# CKLink_Lite.net
KiCad netlist of a schematic drawn in Altium Designer
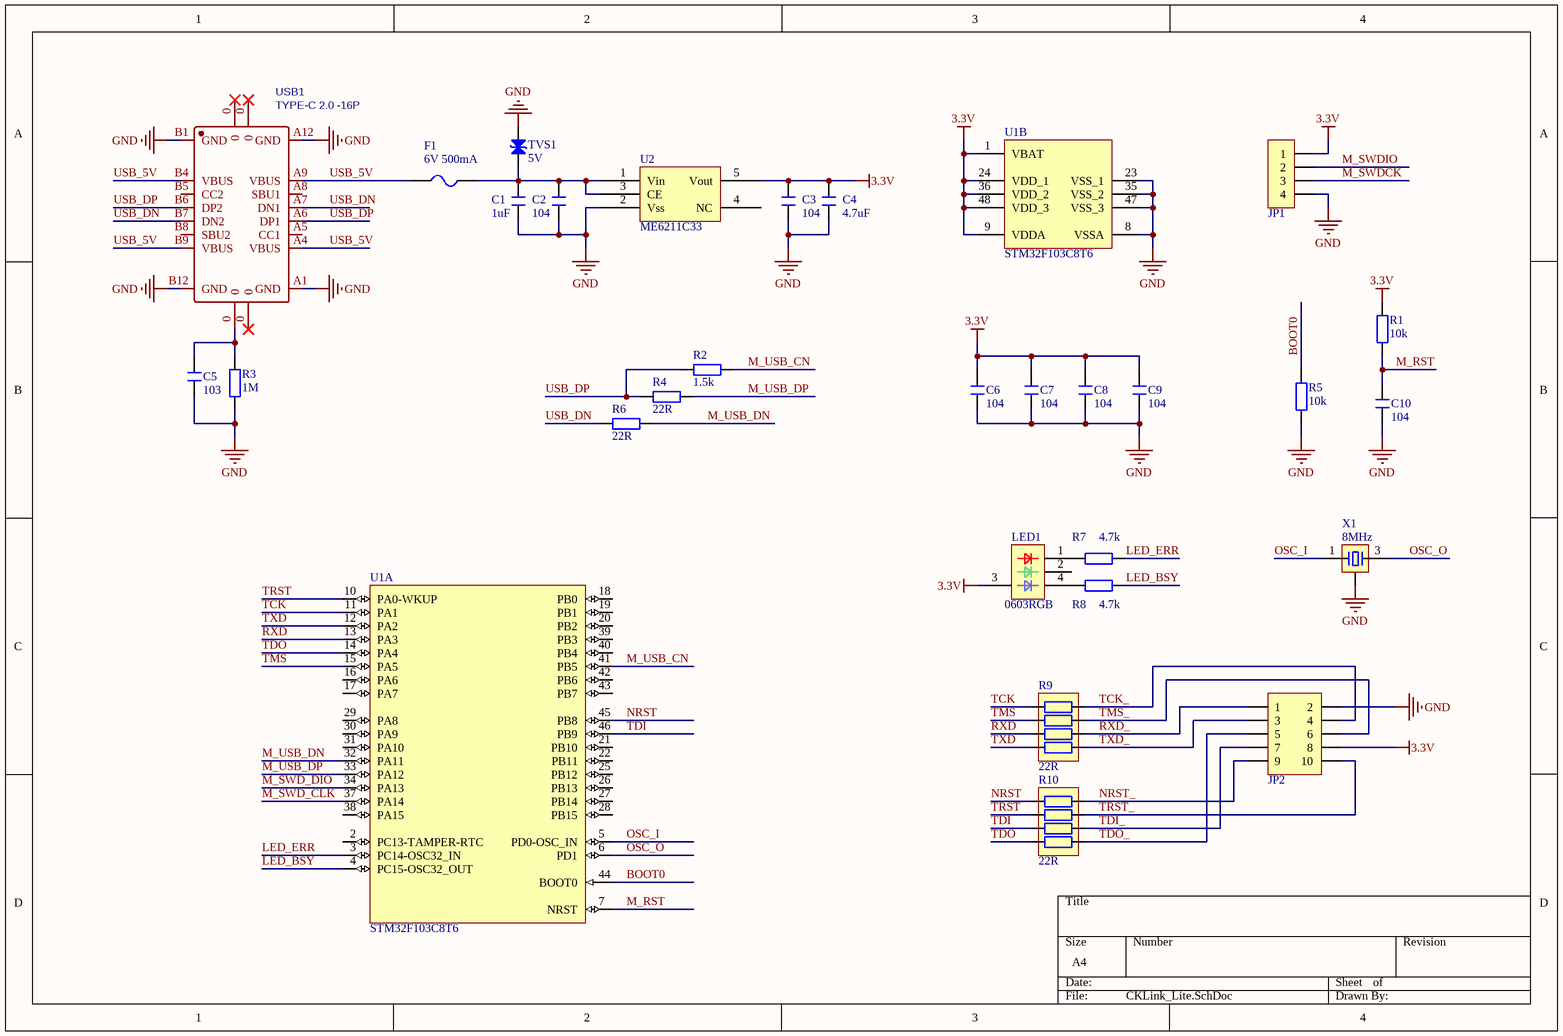
[diagram p0: CKLink_Lite.SchDoc]

(export (version "E")
  (design (tool "Eeschema 10.0.6"))
  (components
    (comp (ref "C1")
      (value "1uF")
      (footprint "C 0603_L")
      (description "贴片电容")
      (libsource (lib "0.1 - 电阻-电容-电感") (part "C"))
    )
    (comp (ref "C2")
      (value "104")
      (footprint "C 0603_L")
      (description "贴片电容")
      (libsource (lib "0.1 - 电阻-电容-电感") (part "C"))
    )
    (comp (ref "C3")
      (value "104")
      (footprint "C 0603_L")
      (description "贴片电容")
      (libsource (lib "0.1 - 电阻-电容-电感") (part "C"))
    )
    (comp (ref "C4")
      (value "4.7uF")
      (footprint "C 0603_L")
      (description "贴片电容")
      (libsource (lib "0.1 - 电阻-电容-电感") (part "C"))
    )
    (comp (ref "C5")
      (value "103")
      (footprint "C 0603_L")
      (description "贴片电容")
      (libsource (lib "0.1 - 电阻-电容-电感") (part "C"))
    )
    (comp (ref "C6")
      (value "104")
      (footprint "C 0603_L")
      (description "贴片电容")
      (libsource (lib "0.1 - 电阻-电容-电感") (part "C"))
    )
    (comp (ref "C7")
      (value "104")
      (footprint "C 0603_L")
      (description "贴片电容")
      (libsource (lib "0.1 - 电阻-电容-电感") (part "C"))
    )
    (comp (ref "C8")
      (value "104")
      (footprint "C 0603_L")
      (description "贴片电容")
      (libsource (lib "0.1 - 电阻-电容-电感") (part "C"))
    )
    (comp (ref "C9")
      (value "104")
      (footprint "C 0603_L")
      (description "贴片电容")
      (libsource (lib "0.1 - 电阻-电容-电感") (part "C"))
    )
    (comp (ref "C10")
      (value "104")
      (footprint "C 0603_L")
      (description "贴片电容")
      (libsource (lib "0.1 - 电阻-电容-电感") (part "C"))
    )
    (comp (ref "F1")
      (value "6V 500mA")
      (footprint "FU 0805")
      (description "贴片保险丝")
      (fields (field (name "版权归属") "封装库来自淘宝卖家 ID：黄晶宝石"))
      (libsource (lib "0.5 - 保险丝-晶振-光耦") (part "FU"))
    )
    (comp (ref "JP1")
      (value "HDR-1X4")
      (footprint "HDR2.54-LI-4P")
      (description "4P接插件")
      (fields (field (name "版权归属") "封装库来自淘宝 ID：黄晶宝石"))
      (libsource (lib "5.4 - 接插件-脚距2.54 (100mil) ") (part "Header 4"))
    )
    (comp (ref "JP2")
      (value "Header 5X2")
      (footprint "CHE2*5")
      (description "5*2P接插件")
      (fields (field (name "版权归属") "封装库来自淘宝 ID：黄晶宝石"))
      (libsource (lib "5.4 - 接插件-脚距2.54 (100mil) ") (part "Header 5X2"))
    )
    (comp (ref "LED1")
      (value "0603RGB")
      (footprint "0603RGB")
      (libsource (lib "0.3 - LED发光二极管") (part "0603RGB"))
    )
    (comp (ref "R1")
      (value "10k")
      (footprint "R 0603_L")
      (description "贴片电阻")
      (libsource (lib "0.1 - 电阻-电容-电感") (part "R"))
    )
    (comp (ref "R2")
      (value "1.5k")
      (footprint "R 0603_L")
      (description "贴片电阻")
      (libsource (lib "0.1 - 电阻-电容-电感") (part "R"))
    )
    (comp (ref "R3")
      (value "1M")
      (footprint "R 0603_L")
      (description "贴片电阻")
      (libsource (lib "0.1 - 电阻-电容-电感") (part "R"))
    )
    (comp (ref "R4")
      (value "22R")
      (footprint "R 0603_L")
      (description "贴片电阻")
      (libsource (lib "0.1 - 电阻-电容-电感") (part "R"))
    )
    (comp (ref "R5")
      (value "10k")
      (footprint "R 0603_L")
      (description "贴片电阻")
      (libsource (lib "0.1 - 电阻-电容-电感") (part "R"))
    )
    (comp (ref "R6")
      (value "22R")
      (footprint "R 0603_L")
      (description "贴片电阻")
      (libsource (lib "0.1 - 电阻-电容-电感") (part "R"))
    )
    (comp (ref "R7")
      (value "4.7k")
      (footprint "R 0603_L")
      (description "贴片电阻")
      (libsource (lib "0.1 - 电阻-电容-电感") (part "R"))
    )
    (comp (ref "R8")
      (value "4.7k")
      (footprint "R 0603_L")
      (description "贴片电阻")
      (libsource (lib "0.1 - 电阻-电容-电感") (part "R"))
    )
    (comp (ref "R9")
      (value "22R")
      (footprint "RCA-8P4R-0603")
      (description "贴片排阻")
      (libsource (lib "0.1 - 电阻-电容-电感") (part "R-8P4R"))
    )
    (comp (ref "R10")
      (value "22R")
      (footprint "RCA-8P4R-0603")
      (description "贴片排阻")
      (libsource (lib "") (part "R-8P4R_1"))
    )
    (comp (ref "TVS1")
      (value "5V")
      (footprint "SOD-323")
      (description "TVS保护")
      (libsource (lib "0.2 - 二极管-整流桥") (part "TVS"))
    )
    (comp (ref "U1")
      (value "STM32F103C8T6")
      (footprint "LQFP48_L")
      (libsource (lib "2.3 - STM32 F1系列单片机") (part "STM32F103C8T6"))
    )
    (comp (ref "U2")
      (value "ME6211C33")
      (footprint "SOT23-5N")
      (description "3.3V 500mA 低压差线性稳压器")
      (libsource (lib "1.1 - 电源类芯片") (part "ME6211C33"))
    )
    (comp (ref "USB1")
      (value "TYPE-C 2.0 -16P")
      (footprint "USB-TYPE-C_16PIN-MALE-TYPE-C-31-M-12")
      (description "USB2.0 Type-C 母座 16Pin")
      (libsource (lib "0.8 - 以太网-音频-USB插座") (part "USB2.0 Type-C 16Pin母座"))
    )
    (comp (ref "X1")
      (value "8MHz")
      (footprint "CSTCE 3pin")
      (description "3脚无源晶振")
      (fields (field (name "版权归属") "封装库来自淘宝卖家 ID：黄晶宝石"))
      (libsource (lib "0.5 - 保险丝-晶振-光耦") (part "XTAL-3P"))
    )
  )
  (nets
    (net (code "1") (name "/BOOT0") (class "Default")
      (node (ref "R5") (pin "2") (pinfunction "2_2") (pintype "passive"))
      (node (ref "U1") (pin "44") (pinfunction "BOOT0_44") (pintype "input"))
    )
    (net (code "2") (name "/LED_BSY") (class "Default")
      (node (ref "R8") (pin "1") (pinfunction "1_1") (pintype "passive"))
      (node (ref "U1") (pin "4") (pinfunction "PC15-OSC32_OUT_4") (pintype "bidirectional"))
    )
    (net (code "3") (name "/LED_ERR") (class "Default")
      (node (ref "R7") (pin "1") (pinfunction "1_1") (pintype "passive"))
      (node (ref "U1") (pin "3") (pinfunction "PC14-OSC32_IN_3") (pintype "bidirectional"))
    )
    (net (code "4") (name "/M_RST") (class "Default")
      (node (ref "C10") (pin "2") (pinfunction "2_2") (pintype "passive"))
      (node (ref "R1") (pin "1") (pinfunction "1_1") (pintype "passive"))
      (node (ref "U1") (pin "7") (pinfunction "NRST_7") (pintype "bidirectional"))
    )
    (net (code "5") (name "/M_SWDCK") (class "Default")
      (node (ref "JP1") (pin "3") (pinfunction "3_3") (pintype "passive"))
    )
    (net (code "6") (name "/M_SWDIO") (class "Default")
      (node (ref "JP1") (pin "2") (pinfunction "2_2") (pintype "passive"))
    )
    (net (code "7") (name "/M_SWD_CLK") (class "Default")
      (node (ref "U1") (pin "37") (pinfunction "PA14_37") (pintype "bidirectional"))
    )
    (net (code "8") (name "/M_SWD_DIO") (class "Default")
      (node (ref "U1") (pin "34") (pinfunction "PA13_34") (pintype "bidirectional"))
    )
    (net (code "9") (name "/M_USB_CN") (class "Default")
      (node (ref "R2") (pin "1") (pinfunction "1_1") (pintype "passive"))
      (node (ref "U1") (pin "41") (pinfunction "PB5_41") (pintype "bidirectional"))
    )
    (net (code "10") (name "/M_USB_DN") (class "Default")
      (node (ref "R6") (pin "1") (pinfunction "1_1") (pintype "passive"))
      (node (ref "U1") (pin "32") (pinfunction "PA11_32") (pintype "bidirectional"))
    )
    (net (code "11") (name "/M_USB_DP") (class "Default")
      (node (ref "R4") (pin "1") (pinfunction "1_1") (pintype "passive"))
      (node (ref "U1") (pin "33") (pinfunction "PA12_33") (pintype "bidirectional"))
    )
    (net (code "12") (name "/NRST") (class "Default")
      (node (ref "R10") (pin "4") (pinfunction "4_4") (pintype "passive"))
      (node (ref "U1") (pin "45") (pinfunction "PB8_45") (pintype "bidirectional"))
    )
    (net (code "13") (name "/NRST_") (class "Default")
      (node (ref "JP2") (pin "9") (pinfunction "9_9") (pintype "passive"))
      (node (ref "R10") (pin "5") (pinfunction "5_5") (pintype "passive"))
    )
    (net (code "14") (name "/OSC_I") (class "Default")
      (node (ref "U1") (pin "5") (pinfunction "PD0-OSC_IN_5") (pintype "bidirectional"))
      (node (ref "X1") (pin "1") (pinfunction "1_1") (pintype "passive"))
    )
    (net (code "15") (name "/OSC_O") (class "Default")
      (node (ref "U1") (pin "6") (pinfunction "PD1_6") (pintype "bidirectional"))
      (node (ref "X1") (pin "3") (pinfunction "3_3") (pintype "passive"))
    )
    (net (code "16") (name "/RXD") (class "Default")
      (node (ref "R9") (pin "3") (pinfunction "3_3") (pintype "passive"))
      (node (ref "U1") (pin "13") (pinfunction "PA3_13") (pintype "bidirectional"))
    )
    (net (code "17") (name "/RXD_") (class "Default")
      (node (ref "JP2") (pin "1") (pinfunction "1_1") (pintype "passive"))
      (node (ref "R9") (pin "6") (pinfunction "6_6") (pintype "passive"))
    )
    (net (code "18") (name "/TCK") (class "Default")
      (node (ref "R9") (pin "1") (pinfunction "1_1") (pintype "passive"))
      (node (ref "U1") (pin "11") (pinfunction "PA1_11") (pintype "bidirectional"))
    )
    (net (code "19") (name "/TCK_") (class "Default")
      (node (ref "JP2") (pin "4") (pinfunction "4_4") (pintype "passive"))
      (node (ref "R9") (pin "8") (pinfunction "8_8") (pintype "passive"))
    )
    (net (code "20") (name "/TDI") (class "Default")
      (node (ref "R10") (pin "2") (pinfunction "2_2") (pintype "passive"))
      (node (ref "U1") (pin "46") (pinfunction "PB9_46") (pintype "bidirectional"))
    )
    (net (code "21") (name "/TDI_") (class "Default")
      (node (ref "JP2") (pin "7") (pinfunction "7_7") (pintype "passive"))
      (node (ref "R10") (pin "7") (pinfunction "7_7") (pintype "passive"))
    )
    (net (code "22") (name "/TDO") (class "Default")
      (node (ref "R10") (pin "1") (pinfunction "1_1") (pintype "passive"))
      (node (ref "U1") (pin "14") (pinfunction "PA4_14") (pintype "bidirectional"))
    )
    (net (code "23") (name "/TDO_") (class "Default")
      (node (ref "JP2") (pin "5") (pinfunction "5_5") (pintype "passive"))
      (node (ref "R10") (pin "8") (pinfunction "8_8") (pintype "passive"))
    )
    (net (code "24") (name "/TMS") (class "Default")
      (node (ref "R9") (pin "2") (pinfunction "2_2") (pintype "passive"))
      (node (ref "U1") (pin "15") (pinfunction "PA5_15") (pintype "bidirectional"))
    )
    (net (code "25") (name "/TMS_") (class "Default")
      (node (ref "JP2") (pin "6") (pinfunction "6_6") (pintype "passive"))
      (node (ref "R9") (pin "7") (pinfunction "7_7") (pintype "passive"))
    )
    (net (code "26") (name "/TRST") (class "Default")
      (node (ref "R10") (pin "3") (pinfunction "3_3") (pintype "passive"))
      (node (ref "U1") (pin "10") (pinfunction "PA0-WKUP_10") (pintype "bidirectional"))
    )
    (net (code "27") (name "/TRST_") (class "Default")
      (node (ref "JP2") (pin "10") (pinfunction "10_10") (pintype "passive"))
      (node (ref "R10") (pin "6") (pinfunction "6_6") (pintype "passive"))
    )
    (net (code "28") (name "/TXD") (class "Default")
      (node (ref "R9") (pin "4") (pinfunction "4_4") (pintype "passive"))
      (node (ref "U1") (pin "12") (pinfunction "PA2_12") (pintype "bidirectional"))
    )
    (net (code "29") (name "/TXD_") (class "Default")
      (node (ref "JP2") (pin "3") (pinfunction "3_3") (pintype "passive"))
      (node (ref "R9") (pin "5") (pinfunction "5_5") (pintype "passive"))
    )
    (net (code "30") (name "/USB_5V") (class "Default")
      (node (ref "F1") (pin "1") (pinfunction "1_1") (pintype "passive"))
      (node (ref "USB1") (pin "A4") (pinfunction "VBUS_A4") (pintype "passive"))
      (node (ref "USB1") (pin "A9") (pinfunction "VBUS_A9") (pintype "passive"))
      (node (ref "USB1") (pin "B4") (pinfunction "VBUS_B4") (pintype "passive"))
      (node (ref "USB1") (pin "B9") (pinfunction "VBUS_B9") (pintype "passive"))
    )
    (net (code "31") (name "/USB_DN") (class "Default")
      (node (ref "R6") (pin "2") (pinfunction "2_2") (pintype "passive"))
      (node (ref "USB1") (pin "A7") (pinfunction "DN1_A7") (pintype "passive"))
      (node (ref "USB1") (pin "B7") (pinfunction "DN2_B7") (pintype "passive"))
    )
    (net (code "32") (name "/USB_DP") (class "Default")
      (node (ref "R2") (pin "2") (pinfunction "2_2") (pintype "passive"))
      (node (ref "R4") (pin "2") (pinfunction "2_2") (pintype "passive"))
      (node (ref "USB1") (pin "A6") (pinfunction "DP1_A6") (pintype "passive"))
      (node (ref "USB1") (pin "B6") (pinfunction "DP2_B6") (pintype "passive"))
    )
    (net (code "33") (name "3.3V") (class "Default")
      (node (ref "C3") (pin "2") (pinfunction "2_2") (pintype "passive"))
      (node (ref "C4") (pin "2") (pinfunction "2_2") (pintype "passive"))
      (node (ref "C6") (pin "2") (pinfunction "2_2") (pintype "passive"))
      (node (ref "C7") (pin "2") (pinfunction "2_2") (pintype "passive"))
      (node (ref "C8") (pin "2") (pinfunction "2_2") (pintype "passive"))
      (node (ref "C9") (pin "2") (pinfunction "2_2") (pintype "passive"))
      (node (ref "JP1") (pin "1") (pinfunction "1_1") (pintype "passive"))
      (node (ref "JP2") (pin "8") (pinfunction "8_8") (pintype "passive"))
      (node (ref "LED1") (pin "3") (pinfunction "VCC_3") (pintype "passive"))
      (node (ref "R1") (pin "2") (pinfunction "2_2") (pintype "passive"))
      (node (ref "U1") (pin "1") (pinfunction "VBAT_1") (pintype "power_in"))
      (node (ref "U1") (pin "24") (pinfunction "VDD_1_24") (pintype "power_in"))
      (node (ref "U1") (pin "36") (pinfunction "VDD_2_36") (pintype "power_in"))
      (node (ref "U1") (pin "48") (pinfunction "VDD_3_48") (pintype "power_in"))
      (node (ref "U1") (pin "9") (pinfunction "VDDA_9") (pintype "power_in"))
      (node (ref "U2") (pin "5") (pinfunction "Vout_5") (pintype "passive"))
    )
    (net (code "34") (name "GND") (class "Default")
      (node (ref "C1") (pin "1") (pinfunction "1_1") (pintype "passive"))
      (node (ref "C10") (pin "1") (pinfunction "1_1") (pintype "passive"))
      (node (ref "C2") (pin "1") (pinfunction "1_1") (pintype "passive"))
      (node (ref "C3") (pin "1") (pinfunction "1_1") (pintype "passive"))
      (node (ref "C4") (pin "1") (pinfunction "1_1") (pintype "passive"))
      (node (ref "C5") (pin "1") (pinfunction "1_1") (pintype "passive"))
      (node (ref "C6") (pin "1") (pinfunction "1_1") (pintype "passive"))
      (node (ref "C7") (pin "1") (pinfunction "1_1") (pintype "passive"))
      (node (ref "C8") (pin "1") (pinfunction "1_1") (pintype "passive"))
      (node (ref "C9") (pin "1") (pinfunction "1_1") (pintype "passive"))
      (node (ref "JP1") (pin "4") (pinfunction "4_4") (pintype "passive"))
      (node (ref "JP2") (pin "2") (pinfunction "2_2") (pintype "passive"))
      (node (ref "R3") (pin "1") (pinfunction "1_1") (pintype "passive"))
      (node (ref "R5") (pin "1") (pinfunction "1_1") (pintype "passive"))
      (node (ref "TVS1") (pin "2") (pinfunction "K_2") (pintype "passive"))
      (node (ref "U1") (pin "23") (pinfunction "VSS_1_23") (pintype "power_in"))
      (node (ref "U1") (pin "35") (pinfunction "VSS_2_35") (pintype "power_in"))
      (node (ref "U1") (pin "47") (pinfunction "VSS_3_47") (pintype "power_in"))
      (node (ref "U1") (pin "8") (pinfunction "VSSA_8") (pintype "power_in"))
      (node (ref "U2") (pin "2") (pinfunction "Vss_2") (pintype "passive"))
      (node (ref "USB1") (pin "A1") (pinfunction "GND_A1") (pintype "passive"))
      (node (ref "USB1") (pin "A12") (pinfunction "GND_A12") (pintype "passive"))
      (node (ref "USB1") (pin "B1") (pinfunction "GND_B1") (pintype "passive"))
      (node (ref "USB1") (pin "B12") (pinfunction "GND_B12") (pintype "passive"))
      (node (ref "X1") (pin "2") (pinfunction "2_2") (pintype "passive"))
    )
    (net (code "35") (name "Net-(C5-Pad2)") (class "Default")
      (node (ref "C5") (pin "2") (pinfunction "2_2") (pintype "passive"))
      (node (ref "R3") (pin "2") (pinfunction "2_2") (pintype "passive"))
      (node (ref "USB1") (pin "0") (pinfunction "0_0") (pintype "passive"))
    )
    (net (code "36") (name "Net-(LED1-B)") (class "Default")
      (node (ref "LED1") (pin "4") (pinfunction "B_4") (pintype "passive"))
      (node (ref "R8") (pin "2") (pinfunction "2_2") (pintype "passive"))
    )
    (net (code "37") (name "Net-(LED1-R)") (class "Default")
      (node (ref "LED1") (pin "1") (pinfunction "R_1") (pintype "passive"))
      (node (ref "R7") (pin "2") (pinfunction "2_2") (pintype "passive"))
    )
    (net (code "38") (name "Net-(TVS1-A)") (class "Default")
      (node (ref "C1") (pin "2") (pinfunction "2_2") (pintype "passive"))
      (node (ref "C2") (pin "2") (pinfunction "2_2") (pintype "passive"))
      (node (ref "F1") (pin "2") (pinfunction "2_2") (pintype "passive"))
      (node (ref "TVS1") (pin "1") (pinfunction "A_1") (pintype "passive"))
      (node (ref "U2") (pin "1") (pinfunction "Vin_1") (pintype "passive"))
      (node (ref "U2") (pin "3") (pinfunction "CE_3") (pintype "passive"))
    )
    (net (code "39") (name "unconnected-(LED1-G-Pad2)") (class "Default")
      (node (ref "LED1") (pin "2") (pinfunction "G_2") (pintype "passive"))
    )
    (net (code "40") (name "unconnected-(U1A-PA6-Pad16)") (class "Default")
      (node (ref "U1") (pin "16") (pinfunction "PA6_16") (pintype "bidirectional"))
    )
    (net (code "41") (name "unconnected-(U1A-PA7-Pad17)") (class "Default")
      (node (ref "U1") (pin "17") (pinfunction "PA7_17") (pintype "bidirectional"))
    )
    (net (code "42") (name "unconnected-(U1A-PA8-Pad29)") (class "Default")
      (node (ref "U1") (pin "29") (pinfunction "PA8_29") (pintype "bidirectional"))
    )
    (net (code "43") (name "unconnected-(U1A-PA9-Pad30)") (class "Default")
      (node (ref "U1") (pin "30") (pinfunction "PA9_30") (pintype "bidirectional"))
    )
    (net (code "44") (name "unconnected-(U1A-PA10-Pad31)") (class "Default")
      (node (ref "U1") (pin "31") (pinfunction "PA10_31") (pintype "bidirectional"))
    )
    (net (code "45") (name "unconnected-(U1A-PA15-Pad38)") (class "Default")
      (node (ref "U1") (pin "38") (pinfunction "PA15_38") (pintype "bidirectional"))
    )
    (net (code "46") (name "unconnected-(U1A-PB0-Pad18)") (class "Default")
      (node (ref "U1") (pin "18") (pinfunction "PB0_18") (pintype "bidirectional"))
    )
    (net (code "47") (name "unconnected-(U1A-PB1-Pad19)") (class "Default")
      (node (ref "U1") (pin "19") (pinfunction "PB1_19") (pintype "bidirectional"))
    )
    (net (code "48") (name "unconnected-(U1A-PB2-Pad20)") (class "Default")
      (node (ref "U1") (pin "20") (pinfunction "PB2_20") (pintype "bidirectional"))
    )
    (net (code "49") (name "unconnected-(U1A-PB3-Pad39)") (class "Default")
      (node (ref "U1") (pin "39") (pinfunction "PB3_39") (pintype "bidirectional"))
    )
    (net (code "50") (name "unconnected-(U1A-PB4-Pad40)") (class "Default")
      (node (ref "U1") (pin "40") (pinfunction "PB4_40") (pintype "bidirectional"))
    )
    (net (code "51") (name "unconnected-(U1A-PB6-Pad42)") (class "Default")
      (node (ref "U1") (pin "42") (pinfunction "PB6_42") (pintype "bidirectional"))
    )
    (net (code "52") (name "unconnected-(U1A-PB7-Pad43)") (class "Default")
      (node (ref "U1") (pin "43") (pinfunction "PB7_43") (pintype "bidirectional"))
    )
    (net (code "53") (name "unconnected-(U1A-PB10-Pad21)") (class "Default")
      (node (ref "U1") (pin "21") (pinfunction "PB10_21") (pintype "bidirectional"))
    )
    (net (code "54") (name "unconnected-(U1A-PB11-Pad22)") (class "Default")
      (node (ref "U1") (pin "22") (pinfunction "PB11_22") (pintype "bidirectional"))
    )
    (net (code "55") (name "unconnected-(U1A-PB12-Pad25)") (class "Default")
      (node (ref "U1") (pin "25") (pinfunction "PB12_25") (pintype "bidirectional"))
    )
    (net (code "56") (name "unconnected-(U1A-PB13-Pad26)") (class "Default")
      (node (ref "U1") (pin "26") (pinfunction "PB13_26") (pintype "bidirectional"))
    )
    (net (code "57") (name "unconnected-(U1A-PB14-Pad27)") (class "Default")
      (node (ref "U1") (pin "27") (pinfunction "PB14_27") (pintype "bidirectional"))
    )
    (net (code "58") (name "unconnected-(U1A-PB15-Pad28)") (class "Default")
      (node (ref "U1") (pin "28") (pinfunction "PB15_28") (pintype "bidirectional"))
    )
    (net (code "59") (name "unconnected-(U1A-PC13-TAMPER-RTC-Pad2)") (class "Default")
      (node (ref "U1") (pin "2") (pinfunction "PC13-TAMPER-RTC_2") (pintype "bidirectional"))
    )
    (net (code "60") (name "unconnected-(U2-NC-Pad4)") (class "Default")
      (node (ref "U2") (pin "4") (pinfunction "NC_4") (pintype "passive"))
    )
    (net (code "61") (name "unconnected-(USB1-CC1-PadA5)") (class "Default")
      (node (ref "USB1") (pin "A5") (pinfunction "CC1_A5") (pintype "passive"))
    )
    (net (code "62") (name "unconnected-(USB1-CC2-PadB5)") (class "Default")
      (node (ref "USB1") (pin "B5") (pinfunction "CC2_B5") (pintype "passive"))
    )
    (net (code "63") (name "unconnected-(USB1-Pad0)") (class "Default")
      (node (ref "USB1") (pin "0") (pinfunction "0_0") (pintype "passive+no_connect"))
    )
    (net (code "64") (name "unconnected-(USB1-Pad0)_1") (class "Default")
      (node (ref "USB1") (pin "0") (pinfunction "0_0") (pintype "passive+no_connect"))
    )
    (net (code "65") (name "unconnected-(USB1-Pad0)_2") (class "Default")
      (node (ref "USB1") (pin "0") (pinfunction "0_0") (pintype "passive+no_connect"))
    )
    (net (code "66") (name "unconnected-(USB1-SBU1-PadA8)") (class "Default")
      (node (ref "USB1") (pin "A8") (pinfunction "SBU1_A8") (pintype "passive"))
    )
    (net (code "67") (name "unconnected-(USB1-SBU2-PadB8)") (class "Default")
      (node (ref "USB1") (pin "B8") (pinfunction "SBU2_B8") (pintype "passive"))
    )
  )
)
